# Current_Sense.net
KiCad netlist of a schematic drawn in Altium Designer
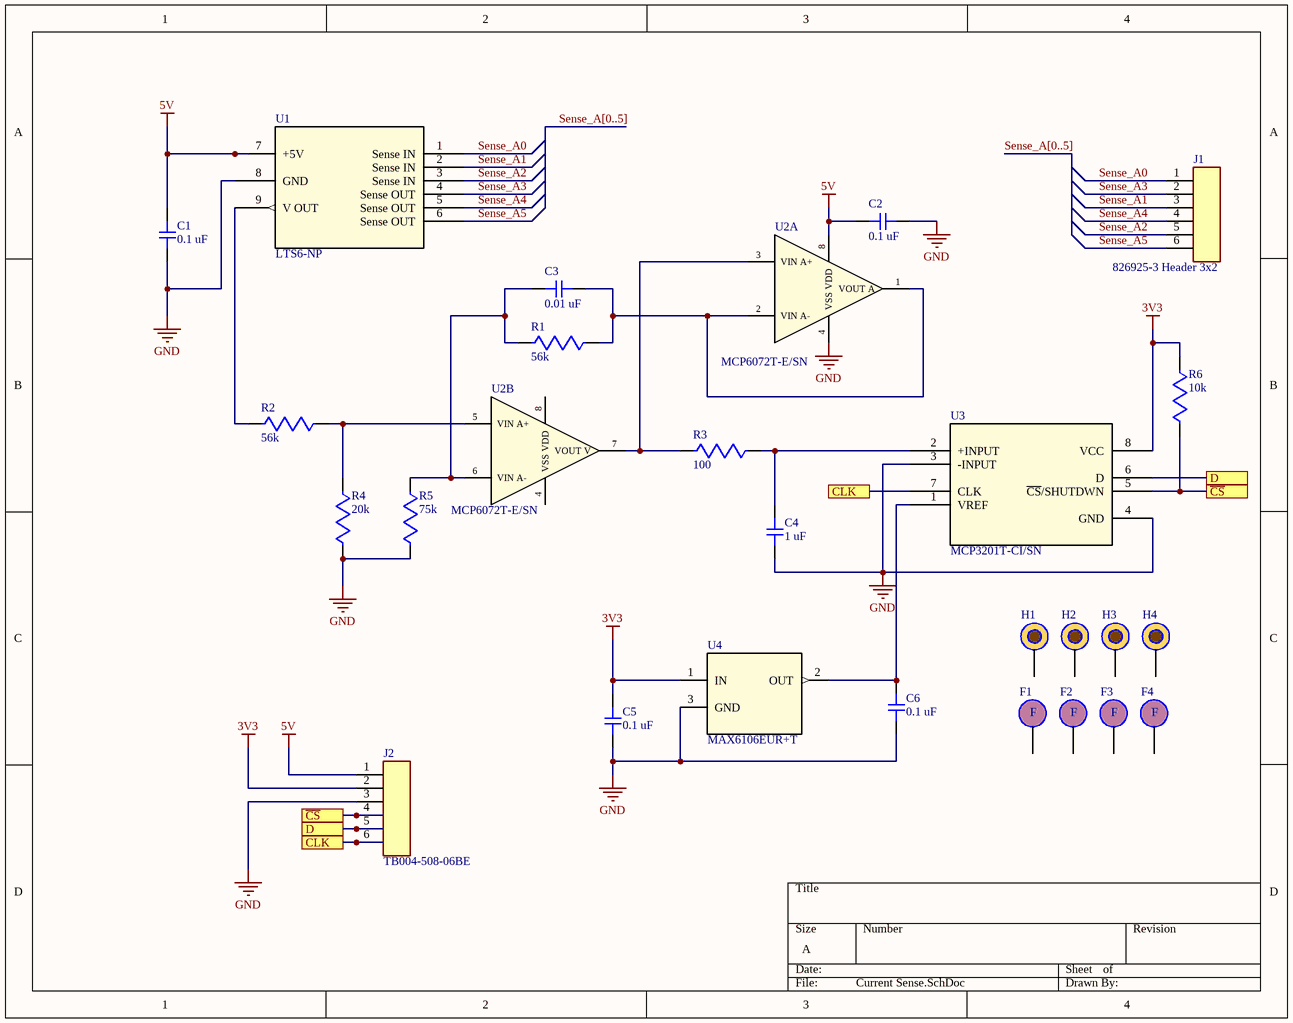
[diagram p0: Current Sense.SchDoc]

(export (version "E")
  (design (tool "Eeschema 10.0.6"))
  (components
    (comp (ref "C1")
      (value "0.1 uF")
      (footprint "C0805E")
      (description "0805 100nF 50 V ±5 % Tolerance X7R Surface Mount Multilayer Ceramic Capacitor")
      (fields
        (field (name "MANUFACTURER") "Kyocera AVX")
        (field (name "MANUFACTURER PART NUMBER") "08055C104JAT2A")
      )
      (libsource (lib "Current Sense") (part "08055C104JAT2A"))
    )
    (comp (ref "C2")
      (value "0.1 uF")
      (footprint "C0805E")
      (description "0805 100nF 50 V ±5 % Tolerance X7R Surface Mount Multilayer Ceramic Capacitor")
      (fields
        (field (name "MANUFACTURER") "Kyocera AVX")
        (field (name "MANUFACTURER PART NUMBER") "08055C104JAT2A")
      )
      (libsource (lib "Current Sense") (part "08055C104JAT2A"))
    )
    (comp (ref "C3")
      (value "0.01 uF")
      (footprint "C0805E")
      (description "0805 0.01 uF 100 V ±5 % Tolerance X7R SMT Multilayer Ceramic Capacitor")
      (fields
        (field (name "MANUFACTURER") "Kyocera AVX")
        (field (name "MANUFACTURER PART NUMBER") "08051C103J4Z2A")
      )
      (libsource (lib "Current Sense") (part "08051C103J4Z2A"))
    )
    (comp (ref "C4")
      (value "1 uF")
      (footprint "C0805E")
      (description "0805 1 uF 25 V ±5 % Tolerance X7R Surface Mount Multilayer Ceramic Capacitor")
      (fields
        (field (name "MANUFACTURER") "Kyocera AVX")
        (field (name "MANUFACTURER PART NUMBER") "08053C105JAT2A")
      )
      (libsource (lib "Current Sense") (part "08053C105JAT2A"))
    )
    (comp (ref "C5")
      (value "0.1 uF")
      (footprint "C0805E")
      (description "0805 100nF 50 V ±5 % Tolerance X7R Surface Mount Multilayer Ceramic Capacitor")
      (fields
        (field (name "MANUFACTURER") "Kyocera AVX")
        (field (name "MANUFACTURER PART NUMBER") "08055C104JAT2A")
      )
      (libsource (lib "Current Sense") (part "08055C104JAT2A"))
    )
    (comp (ref "C6")
      (value "0.1 uF")
      (footprint "C0805E")
      (description "0805 100nF 50 V ±5 % Tolerance X7R Surface Mount Multilayer Ceramic Capacitor")
      (fields
        (field (name "MANUFACTURER") "Kyocera AVX")
        (field (name "MANUFACTURER PART NUMBER") "08055C104JAT2A")
      )
      (libsource (lib "Current Sense") (part "08055C104JAT2A"))
    )
    (comp (ref "F1")
      (value "Fiducial 200mil")
      (footprint "FIDU_100mil")
      (libsource (lib "Current Sense") (part "FIDU_100mil"))
    )
    (comp (ref "F2")
      (value "Fiducial 200mil")
      (footprint "FIDU_100mil")
      (libsource (lib "Current Sense") (part "FIDU_100mil"))
    )
    (comp (ref "F3")
      (value "Fiducial 200mil")
      (footprint "FIDU_100mil")
      (libsource (lib "Current Sense") (part "FIDU_100mil"))
    )
    (comp (ref "F4")
      (value "Fiducial 200mil")
      (footprint "FIDU_100mil")
      (libsource (lib "Current Sense") (part "FIDU_100mil"))
    )
    (comp (ref "H1")
      (value "4-40 Hole")
      (footprint "4-40 Hole")
      (libsource (lib "Current Sense") (part "4-40 Hole"))
    )
    (comp (ref "H2")
      (value "4-40 Hole")
      (footprint "4-40 Hole")
      (libsource (lib "Current Sense") (part "4-40 Hole"))
    )
    (comp (ref "H3")
      (value "4-40 Hole")
      (footprint "4-40 Hole")
      (libsource (lib "Current Sense") (part "4-40 Hole"))
    )
    (comp (ref "H4")
      (value "4-40 Hole")
      (footprint "4-40 Hole")
      (libsource (lib "Current Sense") (part "4-40 Hole"))
    )
    (comp (ref "J1")
      (value "826925-3 Header 3x2")
      (footprint "TE_826925-3")
      (description "Conn Unshrouded Header HDR 6 POS 2.54mm Solder ST Thru-Hole Automotive Carton")
      (fields
        (field (name "MANUFACTURER") "TE Connectivity")
        (field (name "MANUFACTURER PART NUMBER") "826925-3")
      )
      (libsource (lib "Current Sense") (part "826925-3"))
    )
    (comp (ref "J2")
      (value "TB004-508-06BE")
      (footprint "CUI_TB004-508-06BE")
      (description "2~24 Poles, Screw Type, Horizontal, 5.08 Pitch, 24~12 (AWG), Terminal Block Connector")
      (fields (field (name "MANUFACTURER") "CUI"))
      (libsource (lib "Current Sense") (part "TB004-508-06BE"))
    )
    (comp (ref "R1")
      (value "56k")
      (footprint "R0805E")
      (description "Res Thick Film 0805 56K Ohm 1% 0.25W(1/4W) ±100ppm/C Pad SMD Automotive T/R")
      (fields
        (field (name "MANUFACTURER") "KOA Speer")
        (field (name "MANUFACTURER PART NUMBER") "RK73H2ATTD5602F")
      )
      (libsource (lib "Current Sense") (part "RK73H2ATTD5602F"))
    )
    (comp (ref "R2")
      (value "56k")
      (footprint "R0805E")
      (description "Res Thick Film 0805 56K Ohm 1% 0.25W(1/4W) ±100ppm/C Pad SMD Automotive T/R")
      (fields
        (field (name "MANUFACTURER") "KOA Speer")
        (field (name "MANUFACTURER PART NUMBER") "RK73H2ATTD5602F")
      )
      (libsource (lib "Current Sense") (part "RK73H2ATTD5602F"))
    )
    (comp (ref "R3")
      (value "100")
      (footprint "R0805E")
      (description "Res Thin Film 0805 100 Ohm 1% 0.25W(1/4W) ±100ppm/C Sulfur Resistant Pad SMD T/R")
      (fields
        (field (name "MANUFACTURER") "Stackpole Electronics")
        (field (name "MANUFACTURER PART NUMBER") "RNCP0805FTD100R")
      )
      (libsource (lib "Current Sense") (part "RNCP0805FTD100R"))
    )
    (comp (ref "R4")
      (value "20k")
      (footprint "R0805E")
      (description "Res Thin Film 0805 20K Ohm 1% 0.25W(1/4W) ±100ppm/C Sulfur Resistant Pad SMD T/R")
      (fields
        (field (name "MANUFACTURER") "Stackpole Electronics")
        (field (name "MANUFACTURER PART NUMBER") "RNCP0805FTD20K0")
      )
      (libsource (lib "Current Sense") (part "RNCP0805FTD20K0"))
    )
    (comp (ref "R5")
      (value "75k")
      (footprint "R0805E")
      (description "Res Thin Film 0805 75K Ohm 1% 0.25W(1/4W) ±100ppm/C Sulfur Resistant Pad SMD T/R")
      (fields
        (field (name "MANUFACTURER") "Stackpole Electronics")
        (field (name "MANUFACTURER PART NUMBER") "RNCP0805FTD75K0")
      )
      (libsource (lib "Current Sense") (part "RNCP0805FTD75K0"))
    )
    (comp (ref "R6")
      (value "10k")
      (footprint "R0805E")
      (description "Res Thin Film 0805 10K Ohm 1% 1/4W ±100ppm/°C Molded SMD Paper T/R")
      (fields
        (field (name "MANUFACTURER") "Stackpole Electronics")
        (field (name "MANUFACTURER PART NUMBER") "RNCP0805FTD10K0")
      )
      (libsource (lib "Current Sense") (part "RNCP0805FTD10K0"))
    )
    (comp (ref "U1")
      (value "LTS6-NP")
      (footprint "LTS 6-NP_LEM")
      (description "Sensor Current Hall 6A Ac/dc")
      (fields (field (name "MANUFACTURER") "LEM"))
      (libsource (lib "Current Sense") (part "LTS6-NP"))
    )
    (comp (ref "U2")
      (value "MCP6072T-E/SN")
      (footprint "SOIC8-N_MC_MCH")
      (description "Op Amp Dual Precision Amplifier R-R I/O 6V Automotive 8-Pin SOIC N T/R")
      (fields (field (name "MANUFACTURER") "Microchip"))
      (libsource (lib "Current Sense") (part "MCP6072T-E/SN"))
    )
    (comp (ref "U3")
      (value "MCP3201T-CI/SN")
      (footprint "SOIC8-N_MC_MCH")
      (description "1-Channel Single ADC SAR 100ksps 12-bit Serial Automotive 8-Pin SOIC N T/R")
      (fields (field (name "MANUFACTURER") "Microchip"))
      (libsource (lib "Current Sense") (part "MCP3201T-CI/SN"))
    )
    (comp (ref "U4")
      (value "MAX6106EUR+T")
      (footprint "21-0051H_MXM")
      (description "MAX6106 Series 2.056 V ±0.4 % Surface Mount Series Voltage Reference - SOT-23")
      (fields (field (name "MANUFACTURER") "Maxim") (field (name "TOLERANCE") "0.4%"))
      (libsource (lib "Current Sense") (part "MAX6106EUR+T"))
    )
  )
  (nets
    (net (code "1") (name "/CLK") (class "Default")
      (node (ref "J2") (pin "6") (pinfunction "6_6") (pintype "passive"))
      (node (ref "U3") (pin "7") (pinfunction "CLK_7") (pintype "passive"))
    )
    (net (code "2") (name "/D") (class "Default")
      (node (ref "J2") (pin "5") (pinfunction "5_5") (pintype "passive"))
      (node (ref "U3") (pin "6") (pinfunction "D_6") (pintype "passive"))
    )
    (net (code "3") (name "/Sense_A0") (class "Default")
      (node (ref "J1") (pin "1") (pintype "passive"))
      (node (ref "U1") (pin "1") (pinfunction "Sense_IN_1") (pintype "passive"))
    )
    (net (code "4") (name "/Sense_A1") (class "Default")
      (node (ref "J1") (pin "3") (pintype "passive"))
      (node (ref "U1") (pin "2") (pinfunction "Sense_IN_2") (pintype "passive"))
    )
    (net (code "5") (name "/Sense_A2") (class "Default")
      (node (ref "J1") (pin "5") (pintype "passive"))
      (node (ref "U1") (pin "3") (pinfunction "Sense_IN_3") (pintype "passive"))
    )
    (net (code "6") (name "/Sense_A3") (class "Default")
      (node (ref "J1") (pin "2") (pintype "passive"))
      (node (ref "U1") (pin "4") (pinfunction "Sense_OUT_4") (pintype "passive"))
    )
    (net (code "7") (name "/Sense_A4") (class "Default")
      (node (ref "J1") (pin "4") (pintype "passive"))
      (node (ref "U1") (pin "5") (pinfunction "Sense_OUT_5") (pintype "passive"))
    )
    (net (code "8") (name "/Sense_A5") (class "Default")
      (node (ref "J1") (pin "6") (pintype "passive"))
      (node (ref "U1") (pin "6") (pinfunction "Sense_OUT_6") (pintype "passive"))
    )
    (net (code "10") (name "/~{CS}") (class "Default")
      (node (ref "J2") (pin "4") (pinfunction "4_4") (pintype "passive"))
      (node (ref "R6") (pin "1") (pinfunction "1_1") (pintype "passive"))
      (node (ref "U3") (pin "5") (pinfunction "~{CS}/SHUTDWN_5") (pintype "passive"))
    )
    (net (code "11") (name "3V3") (class "Default")
      (node (ref "C5") (pin "2") (pinfunction "2_2") (pintype "passive"))
      (node (ref "J2") (pin "2") (pinfunction "2_2") (pintype "passive"))
      (node (ref "R6") (pin "2") (pinfunction "2_2") (pintype "passive"))
      (node (ref "U3") (pin "8") (pinfunction "VCC_8") (pintype "passive"))
      (node (ref "U4") (pin "1") (pinfunction "IN_1") (pintype "power_in"))
    )
    (net (code "12") (name "5V") (class "Default")
      (node (ref "C1") (pin "2") (pinfunction "2_2") (pintype "passive"))
      (node (ref "C2") (pin "2") (pinfunction "2_2") (pintype "passive"))
      (node (ref "J2") (pin "1") (pinfunction "1_1") (pintype "passive"))
      (node (ref "U1") (pin "7") (pinfunction "+5V_7") (pintype "power_in"))
      (node (ref "U2") (pin "8") (pinfunction "VDD_8") (pintype "power_in"))
    )
    (net (code "13") (name "GND") (class "Default")
      (node (ref "C1") (pin "1") (pinfunction "1_1") (pintype "passive"))
      (node (ref "C2") (pin "1") (pinfunction "1_1") (pintype "passive"))
      (node (ref "C4") (pin "1") (pinfunction "1_1") (pintype "passive"))
      (node (ref "C5") (pin "1") (pinfunction "1_1") (pintype "passive"))
      (node (ref "C6") (pin "1") (pinfunction "1_1") (pintype "passive"))
      (node (ref "J2") (pin "3") (pinfunction "3_3") (pintype "passive"))
      (node (ref "R4") (pin "2") (pinfunction "2_2") (pintype "passive"))
      (node (ref "R5") (pin "1") (pinfunction "1_1") (pintype "passive"))
      (node (ref "U1") (pin "8") (pinfunction "GND_8") (pintype "power_in"))
      (node (ref "U2") (pin "4") (pinfunction "VSS_4") (pintype "power_in"))
      (node (ref "U3") (pin "3") (pinfunction "-INPUT_3") (pintype "passive"))
      (node (ref "U3") (pin "4") (pinfunction "GND_4") (pintype "passive"))
      (node (ref "U4") (pin "3") (pinfunction "GND_3") (pintype "power_in"))
    )
    (net (code "14") (name "Net-(U1-V_OUT)") (class "Default")
      (node (ref "R2") (pin "1") (pinfunction "1_1") (pintype "passive"))
      (node (ref "U1") (pin "9") (pinfunction "V_OUT_9") (pintype "output"))
    )
    (net (code "15") (name "Net-(U2A-VIN_A+)") (class "Default")
      (node (ref "R3") (pin "1") (pinfunction "1_1") (pintype "passive"))
      (node (ref "U2") (pin "3") (pinfunction "VIN_A+_3") (pintype "passive"))
      (node (ref "U2") (pin "7") (pinfunction "VOUT_V_7") (pintype "passive"))
    )
    (net (code "16") (name "Net-(U2A-VIN_A-)") (class "Default")
      (node (ref "C3") (pin "2") (pinfunction "2_2") (pintype "passive"))
      (node (ref "R1") (pin "2") (pinfunction "2_2") (pintype "passive"))
      (node (ref "U2") (pin "1") (pinfunction "VOUT_A_1") (pintype "passive"))
      (node (ref "U2") (pin "2") (pinfunction "VIN_A-_2") (pintype "passive"))
    )
    (net (code "17") (name "Net-(U2B-VIN_A+)") (class "Default")
      (node (ref "R2") (pin "2") (pinfunction "2_2") (pintype "passive"))
      (node (ref "R4") (pin "1") (pinfunction "1_1") (pintype "passive"))
      (node (ref "U2") (pin "5") (pinfunction "VIN_A+_5") (pintype "passive"))
    )
    (net (code "18") (name "Net-(U2B-VIN_A-)") (class "Default")
      (node (ref "C3") (pin "1") (pinfunction "1_1") (pintype "passive"))
      (node (ref "R1") (pin "1") (pinfunction "1_1") (pintype "passive"))
      (node (ref "R5") (pin "2") (pinfunction "2_2") (pintype "passive"))
      (node (ref "U2") (pin "6") (pinfunction "VIN_A-_6") (pintype "passive"))
    )
    (net (code "19") (name "Net-(U3-+INPUT)") (class "Default")
      (node (ref "C4") (pin "2") (pinfunction "2_2") (pintype "passive"))
      (node (ref "R3") (pin "2") (pinfunction "2_2") (pintype "passive"))
      (node (ref "U3") (pin "2") (pinfunction "+INPUT_2") (pintype "passive"))
    )
    (net (code "20") (name "Net-(U3-VREF)") (class "Default")
      (node (ref "C6") (pin "2") (pinfunction "2_2") (pintype "passive"))
      (node (ref "U3") (pin "1") (pinfunction "VREF_1") (pintype "passive"))
      (node (ref "U4") (pin "2") (pinfunction "OUT_2") (pintype "output"))
    )
    (net (code "21") (name "unconnected-(F1-PadF)") (class "Default")
      (node (ref "F1") (pin "F") (pinfunction "F_F") (pintype "passive"))
    )
    (net (code "22") (name "unconnected-(F2-PadF)") (class "Default")
      (node (ref "F2") (pin "F") (pinfunction "F_F") (pintype "passive"))
    )
    (net (code "23") (name "unconnected-(F3-PadF)") (class "Default")
      (node (ref "F3") (pin "F") (pinfunction "F_F") (pintype "passive"))
    )
    (net (code "24") (name "unconnected-(F4-PadF)") (class "Default")
      (node (ref "F4") (pin "F") (pinfunction "F_F") (pintype "passive"))
    )
    (net (code "25") (name "unconnected-(H1-PadH)") (class "Default")
      (node (ref "H1") (pin "H") (pinfunction "H_H") (pintype "passive"))
    )
    (net (code "26") (name "unconnected-(H2-PadH)") (class "Default")
      (node (ref "H2") (pin "H") (pinfunction "H_H") (pintype "passive"))
    )
    (net (code "27") (name "unconnected-(H3-PadH)") (class "Default")
      (node (ref "H3") (pin "H") (pinfunction "H_H") (pintype "passive"))
    )
    (net (code "28") (name "unconnected-(H4-PadH)") (class "Default")
      (node (ref "H4") (pin "H") (pinfunction "H_H") (pintype "passive"))
    )
    (net (code "29") (name "unconnected-(U2B-VDD-Pad8)") (class "Default")
      (node (ref "U2") (pin "8") (pinfunction "VDD_8") (pintype "power_in"))
    )
    (net (code "30") (name "unconnected-(U2B-VSS-Pad4)") (class "Default")
      (node (ref "U2") (pin "4") (pinfunction "VSS_4") (pintype "power_in"))
    )
  )
)
